# Output_Mixer_v1_1.net
KiCad netlist of a schematic drawn in EAGLE
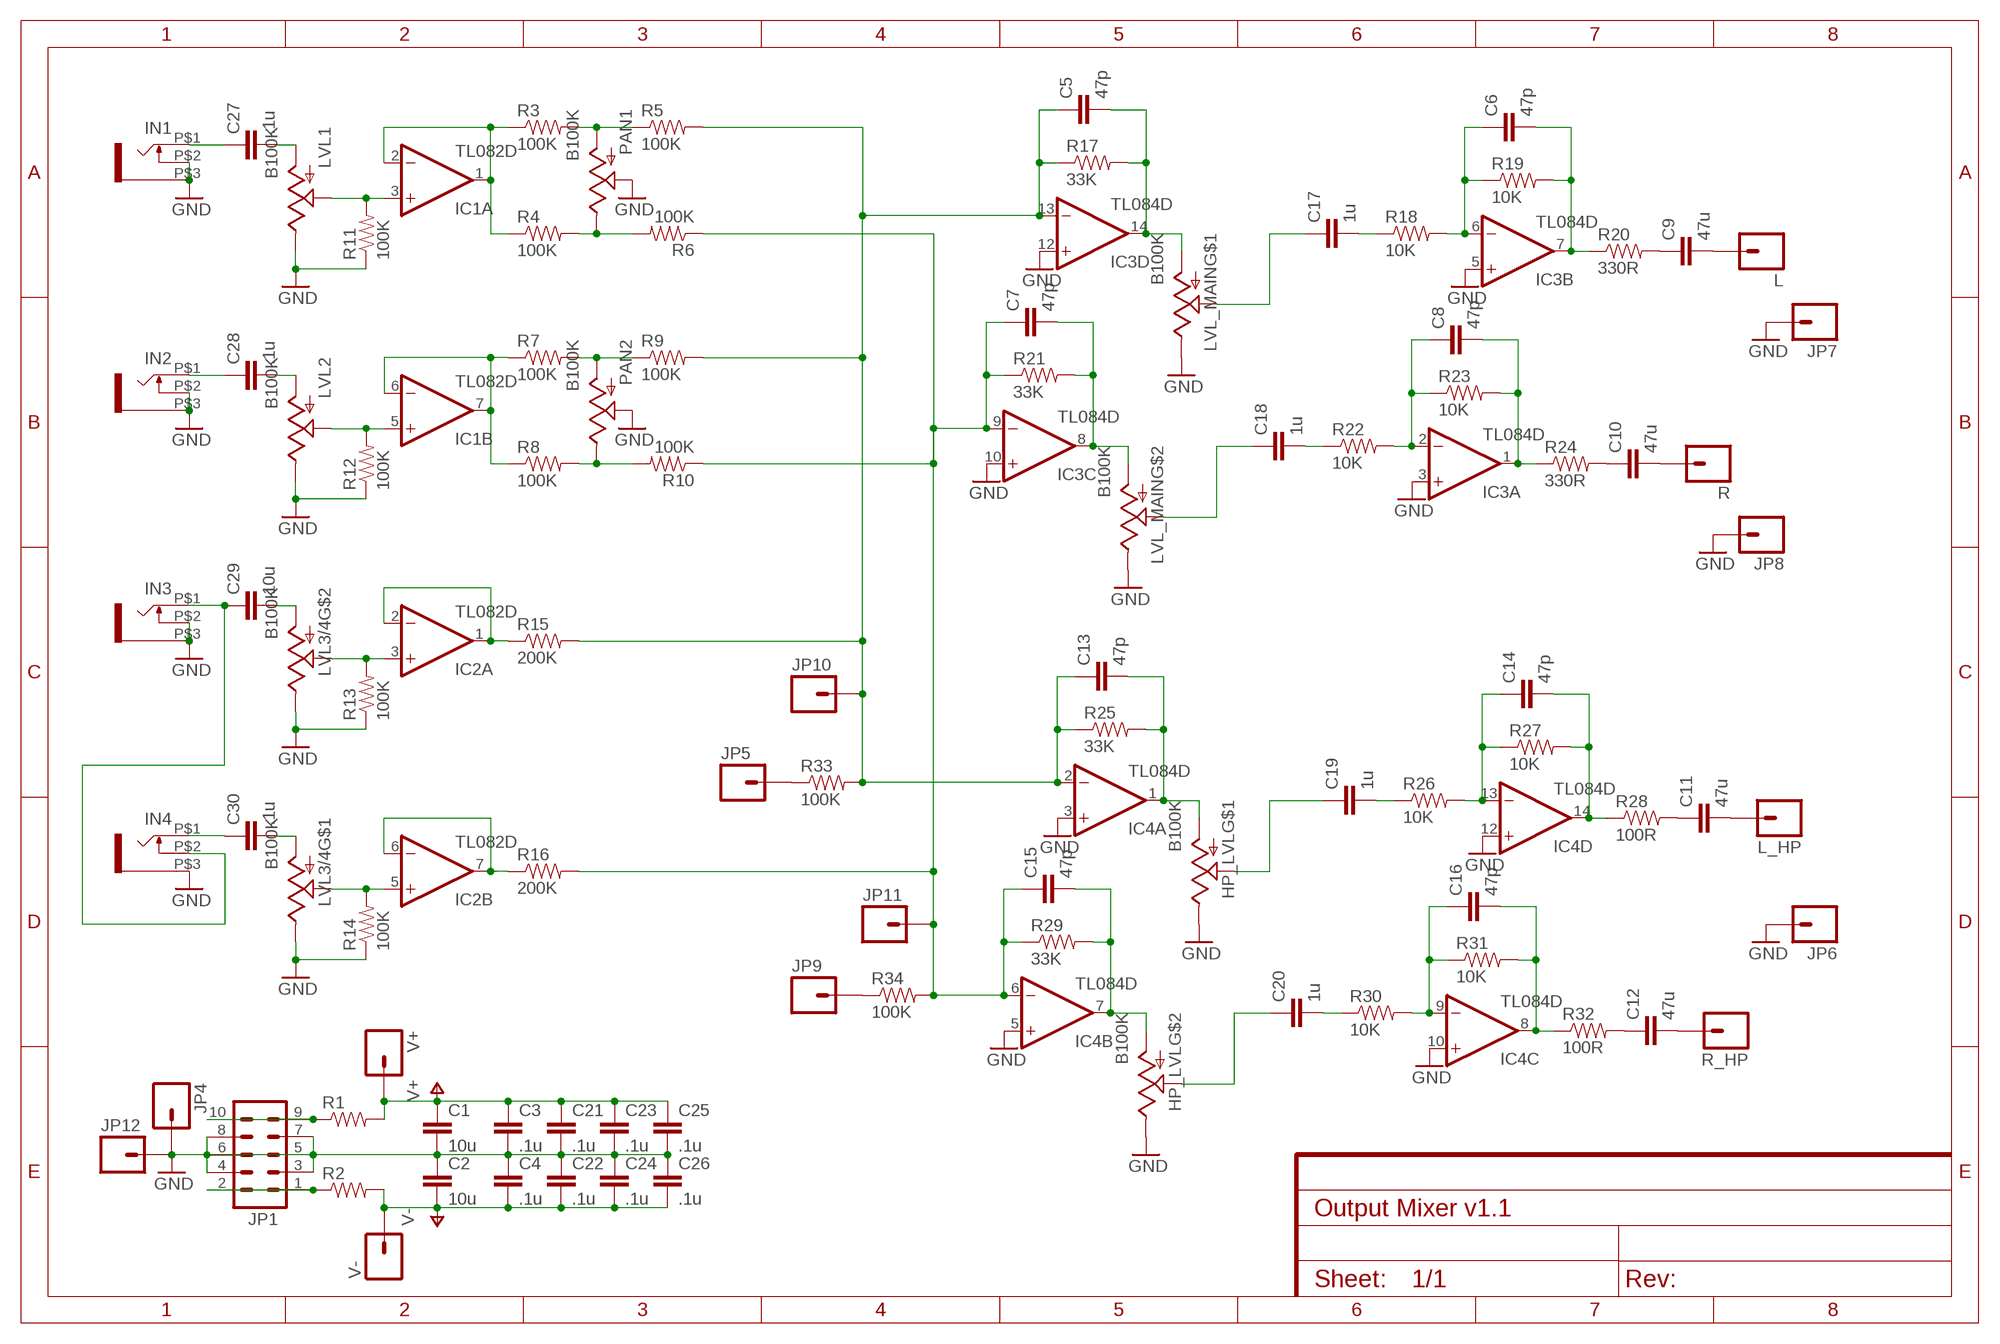
[diagram p0: schematic, sheet 1]

(export (version "E")
  (design (tool "Eeschema 10.0.6"))
  (components
    (comp (ref "C1")
      (value "10u")
      (footprint "eagle-import:1206")
      (libsource (lib "eagle-import") (part "CAP1206"))
    )
    (comp (ref "C2")
      (value "10u")
      (footprint "eagle-import:1206")
      (libsource (lib "eagle-import") (part "CAP1206"))
    )
    (comp (ref "C3")
      (value ".1u")
      (footprint "eagle-import:0805")
      (libsource (lib "eagle-import") (part "CAP0805"))
    )
    (comp (ref "C4")
      (value ".1u")
      (footprint "eagle-import:0805")
      (libsource (lib "eagle-import") (part "CAP0805"))
    )
    (comp (ref "C5")
      (value "47p")
      (footprint "eagle-import:0805")
      (libsource (lib "eagle-import") (part "CAP0805"))
    )
    (comp (ref "C6")
      (value "47p")
      (footprint "eagle-import:0805")
      (libsource (lib "eagle-import") (part "CAP0805"))
    )
    (comp (ref "C7")
      (value "47p")
      (footprint "eagle-import:0805")
      (libsource (lib "eagle-import") (part "CAP0805"))
    )
    (comp (ref "C8")
      (value "47p")
      (footprint "eagle-import:0805")
      (libsource (lib "eagle-import") (part "CAP0805"))
    )
    (comp (ref "C9")
      (value "47u")
      (footprint "eagle-import:1206")
      (libsource (lib "eagle-import") (part "CAP1206"))
    )
    (comp (ref "C10")
      (value "47u")
      (footprint "eagle-import:1206")
      (libsource (lib "eagle-import") (part "CAP1206"))
    )
    (comp (ref "C11")
      (value "47u")
      (footprint "eagle-import:1206")
      (libsource (lib "eagle-import") (part "CAP1206"))
    )
    (comp (ref "C12")
      (value "47u")
      (footprint "eagle-import:1206")
      (libsource (lib "eagle-import") (part "CAP1206"))
    )
    (comp (ref "C13")
      (value "47p")
      (footprint "eagle-import:0805")
      (libsource (lib "eagle-import") (part "CAP0805"))
    )
    (comp (ref "C14")
      (value "47p")
      (footprint "eagle-import:0805")
      (libsource (lib "eagle-import") (part "CAP0805"))
    )
    (comp (ref "C15")
      (value "47p")
      (footprint "eagle-import:0805")
      (libsource (lib "eagle-import") (part "CAP0805"))
    )
    (comp (ref "C16")
      (value "47p")
      (footprint "eagle-import:0805")
      (libsource (lib "eagle-import") (part "CAP0805"))
    )
    (comp (ref "C17")
      (value "1u")
      (footprint "eagle-import:0805")
      (libsource (lib "eagle-import") (part "CAP0805"))
    )
    (comp (ref "C18")
      (value "1u")
      (footprint "eagle-import:0805")
      (libsource (lib "eagle-import") (part "CAP0805"))
    )
    (comp (ref "C19")
      (value "1u")
      (footprint "eagle-import:0805")
      (libsource (lib "eagle-import") (part "CAP0805"))
    )
    (comp (ref "C20")
      (value "1u")
      (footprint "eagle-import:0805")
      (libsource (lib "eagle-import") (part "CAP0805"))
    )
    (comp (ref "C21")
      (value ".1u")
      (footprint "eagle-import:0805")
      (libsource (lib "eagle-import") (part "CAP0805"))
    )
    (comp (ref "C22")
      (value ".1u")
      (footprint "eagle-import:0805")
      (libsource (lib "eagle-import") (part "CAP0805"))
    )
    (comp (ref "C23")
      (value ".1u")
      (footprint "eagle-import:0805")
      (libsource (lib "eagle-import") (part "CAP0805"))
    )
    (comp (ref "C24")
      (value ".1u")
      (footprint "eagle-import:0805")
      (libsource (lib "eagle-import") (part "CAP0805"))
    )
    (comp (ref "C25")
      (value ".1u")
      (footprint "eagle-import:0805")
      (libsource (lib "eagle-import") (part "CAP0805"))
    )
    (comp (ref "C26")
      (value ".1u")
      (footprint "eagle-import:0805")
      (libsource (lib "eagle-import") (part "CAP0805"))
    )
    (comp (ref "C27")
      (value ".1u")
      (footprint "eagle-import:1206")
      (libsource (lib "eagle-import") (part "CAP1206"))
    )
    (comp (ref "C28")
      (value ".1u")
      (footprint "eagle-import:1206")
      (libsource (lib "eagle-import") (part "CAP1206"))
    )
    (comp (ref "C29")
      (value "10u")
      (footprint "eagle-import:1206")
      (libsource (lib "eagle-import") (part "CAP1206"))
    )
    (comp (ref "C30")
      (value ".1u")
      (footprint "eagle-import:1206")
      (libsource (lib "eagle-import") (part "CAP1206"))
    )
    (comp (ref "HP_LVL")
      (value "B100K")
      (footprint "eagle-import:ALPS_ALPHA_POT_DUAL")
      (libsource (lib "eagle-import") (part "POT_DUAL_ALPHA"))
    )
    (comp (ref "IC1")
      (value "TL082D")
      (footprint "eagle-import:SO08")
      (libsource (lib "eagle-import") (part "TL082D"))
    )
    (comp (ref "IC2")
      (value "TL082D")
      (footprint "eagle-import:SO08")
      (libsource (lib "eagle-import") (part "TL082D"))
    )
    (comp (ref "IC3")
      (value "TL084D")
      (footprint "eagle-import:SO14")
      (libsource (lib "eagle-import") (part "TL084D"))
    )
    (comp (ref "IC4")
      (value "TL084D")
      (footprint "eagle-import:SO14")
      (libsource (lib "eagle-import") (part "TL084D"))
    )
    (comp (ref "IN1")
      (value "WQP-PJ301M-12_JACK")
      (footprint "eagle-import:WQP-PJ301M-12_JACK")
      (libsource (lib "eagle-import") (part "WQP-PJ301M-12_JACK"))
    )
    (comp (ref "IN2")
      (value "WQP-PJ301M-12_JACK")
      (footprint "eagle-import:WQP-PJ301M-12_JACK")
      (libsource (lib "eagle-import") (part "WQP-PJ301M-12_JACK"))
    )
    (comp (ref "IN3")
      (value "WQP-PJ301M-12_JACK")
      (footprint "eagle-import:WQP-PJ301M-12_JACK")
      (libsource (lib "eagle-import") (part "WQP-PJ301M-12_JACK"))
    )
    (comp (ref "IN4")
      (value "WQP-PJ301M-12_JACK")
      (footprint "eagle-import:WQP-PJ301M-12_JACK")
      (libsource (lib "eagle-import") (part "WQP-PJ301M-12_JACK"))
    )
    (comp (ref "JP1")
      (value "M05X2PTH")
      (footprint "eagle-import:AVR_ICSP")
      (libsource (lib "eagle-import") (part "M05X2PTH"))
    )
    (comp (ref "JP4")
      (value "M01PTH")
      (footprint "eagle-import:1X01")
      (libsource (lib "eagle-import") (part "M01PTH"))
    )
    (comp (ref "JP5")
      (value "M01PTH")
      (footprint "eagle-import:1X01")
      (libsource (lib "eagle-import") (part "M01PTH"))
    )
    (comp (ref "JP6")
      (value "M01PTH")
      (footprint "eagle-import:1X01")
      (libsource (lib "eagle-import") (part "M01PTH"))
    )
    (comp (ref "JP7")
      (value "M01PTH")
      (footprint "eagle-import:1X01")
      (libsource (lib "eagle-import") (part "M01PTH"))
    )
    (comp (ref "JP8")
      (value "M01PTH")
      (footprint "eagle-import:1X01")
      (libsource (lib "eagle-import") (part "M01PTH"))
    )
    (comp (ref "JP9")
      (value "M01PTH")
      (footprint "eagle-import:1X01")
      (libsource (lib "eagle-import") (part "M01PTH"))
    )
    (comp (ref "JP10")
      (value "M01PTH")
      (footprint "eagle-import:1X01")
      (libsource (lib "eagle-import") (part "M01PTH"))
    )
    (comp (ref "JP11")
      (value "M01PTH")
      (footprint "eagle-import:1X01")
      (libsource (lib "eagle-import") (part "M01PTH"))
    )
    (comp (ref "JP12")
      (value "M01PTH")
      (footprint "eagle-import:1X01")
      (libsource (lib "eagle-import") (part "M01PTH"))
    )
    (comp (ref "L")
      (value "M01PTH")
      (footprint "eagle-import:1X01")
      (libsource (lib "eagle-import") (part "M01PTH"))
    )
    (comp (ref "LVL1")
      (value "B100K")
      (footprint "eagle-import:ALPS_POT")
      (libsource (lib "eagle-import") (part "POT"))
    )
    (comp (ref "LVL2")
      (value "B100K")
      (footprint "eagle-import:ALPS_POT")
      (libsource (lib "eagle-import") (part "POT"))
    )
    (comp (ref "LVL3/4")
      (value "B100K")
      (footprint "eagle-import:ALPS_ALPHA_POT_DUAL")
      (libsource (lib "eagle-import") (part "POT_DUAL_ALPHA"))
    )
    (comp (ref "LVL_MAIN")
      (value "B100K")
      (footprint "eagle-import:ALPS_ALPHA_POT_DUAL")
      (libsource (lib "eagle-import") (part "POT_DUAL_ALPHA"))
    )
    (comp (ref "L_HP")
      (value "M01PTH")
      (footprint "eagle-import:1X01")
      (libsource (lib "eagle-import") (part "M01PTH"))
    )
    (comp (ref "PAN1")
      (value "B100K")
      (footprint "eagle-import:ALPS_POT")
      (libsource (lib "eagle-import") (part "POT"))
    )
    (comp (ref "PAN2")
      (value "B100K")
      (footprint "eagle-import:ALPS_POT")
      (libsource (lib "eagle-import") (part "POT"))
    )
    (comp (ref "R")
      (value "M01PTH")
      (footprint "eagle-import:1X01")
      (libsource (lib "eagle-import") (part "M01PTH"))
    )
    (comp (ref "R1")
      (value "RESISTOR0805-RES")
      (footprint "eagle-import:0805")
      (libsource (lib "eagle-import") (part "RESISTOR0805-RES"))
    )
    (comp (ref "R2")
      (value "RESISTOR0805-RES")
      (footprint "eagle-import:0805")
      (libsource (lib "eagle-import") (part "RESISTOR0805-RES"))
    )
    (comp (ref "R3")
      (value "100K")
      (footprint "eagle-import:0805")
      (libsource (lib "eagle-import") (part "RESISTOR0805-RES"))
    )
    (comp (ref "R4")
      (value "100K")
      (footprint "eagle-import:0805")
      (libsource (lib "eagle-import") (part "RESISTOR0805-RES"))
    )
    (comp (ref "R5")
      (value "100K")
      (footprint "eagle-import:0805")
      (libsource (lib "eagle-import") (part "RESISTOR0805-RES"))
    )
    (comp (ref "R6")
      (value "100K")
      (footprint "eagle-import:0805")
      (libsource (lib "eagle-import") (part "RESISTOR0805-RES"))
    )
    (comp (ref "R7")
      (value "100K")
      (footprint "eagle-import:0805")
      (libsource (lib "eagle-import") (part "RESISTOR0805-RES"))
    )
    (comp (ref "R8")
      (value "100K")
      (footprint "eagle-import:0805")
      (libsource (lib "eagle-import") (part "RESISTOR0805-RES"))
    )
    (comp (ref "R9")
      (value "100K")
      (footprint "eagle-import:0805")
      (libsource (lib "eagle-import") (part "RESISTOR0805-RES"))
    )
    (comp (ref "R10")
      (value "100K")
      (footprint "eagle-import:0805")
      (libsource (lib "eagle-import") (part "RESISTOR0805-RES"))
    )
    (comp (ref "R11")
      (value "100K")
      (footprint "eagle-import:0805")
      (libsource (lib "eagle-import") (part "RESISTOR0805-RES"))
    )
    (comp (ref "R12")
      (value "100K")
      (footprint "eagle-import:0805")
      (libsource (lib "eagle-import") (part "RESISTOR0805-RES"))
    )
    (comp (ref "R13")
      (value "100K")
      (footprint "eagle-import:0805")
      (libsource (lib "eagle-import") (part "RESISTOR0805-RES"))
    )
    (comp (ref "R14")
      (value "100K")
      (footprint "eagle-import:0805")
      (libsource (lib "eagle-import") (part "RESISTOR0805-RES"))
    )
    (comp (ref "R15")
      (value "200K")
      (footprint "eagle-import:0805")
      (libsource (lib "eagle-import") (part "RESISTOR0805-RES"))
    )
    (comp (ref "R16")
      (value "200K")
      (footprint "eagle-import:0805")
      (libsource (lib "eagle-import") (part "RESISTOR0805-RES"))
    )
    (comp (ref "R17")
      (value "33K")
      (footprint "eagle-import:0805")
      (libsource (lib "eagle-import") (part "RESISTOR0805-RES"))
    )
    (comp (ref "R18")
      (value "10K")
      (footprint "eagle-import:0805")
      (libsource (lib "eagle-import") (part "RESISTOR0805-RES"))
    )
    (comp (ref "R19")
      (value "10K")
      (footprint "eagle-import:0805")
      (libsource (lib "eagle-import") (part "RESISTOR0805-RES"))
    )
    (comp (ref "R20")
      (value "330R")
      (footprint "eagle-import:0805")
      (libsource (lib "eagle-import") (part "RESISTOR0805-RES"))
    )
    (comp (ref "R21")
      (value "33K")
      (footprint "eagle-import:0805")
      (libsource (lib "eagle-import") (part "RESISTOR0805-RES"))
    )
    (comp (ref "R22")
      (value "10K")
      (footprint "eagle-import:0805")
      (libsource (lib "eagle-import") (part "RESISTOR0805-RES"))
    )
    (comp (ref "R23")
      (value "10K")
      (footprint "eagle-import:0805")
      (libsource (lib "eagle-import") (part "RESISTOR0805-RES"))
    )
    (comp (ref "R24")
      (value "330R")
      (footprint "eagle-import:0805")
      (libsource (lib "eagle-import") (part "RESISTOR0805-RES"))
    )
    (comp (ref "R25")
      (value "33K")
      (footprint "eagle-import:0805")
      (libsource (lib "eagle-import") (part "RESISTOR0805-RES"))
    )
    (comp (ref "R26")
      (value "10K")
      (footprint "eagle-import:0805")
      (libsource (lib "eagle-import") (part "RESISTOR0805-RES"))
    )
    (comp (ref "R27")
      (value "10K")
      (footprint "eagle-import:0805")
      (libsource (lib "eagle-import") (part "RESISTOR0805-RES"))
    )
    (comp (ref "R28")
      (value "100R")
      (footprint "eagle-import:0805")
      (libsource (lib "eagle-import") (part "RESISTOR0805-RES"))
    )
    (comp (ref "R29")
      (value "33K")
      (footprint "eagle-import:0805")
      (libsource (lib "eagle-import") (part "RESISTOR0805-RES"))
    )
    (comp (ref "R30")
      (value "10K")
      (footprint "eagle-import:0805")
      (libsource (lib "eagle-import") (part "RESISTOR0805-RES"))
    )
    (comp (ref "R31")
      (value "10K")
      (footprint "eagle-import:0805")
      (libsource (lib "eagle-import") (part "RESISTOR0805-RES"))
    )
    (comp (ref "R32")
      (value "100R")
      (footprint "eagle-import:0805")
      (libsource (lib "eagle-import") (part "RESISTOR0805-RES"))
    )
    (comp (ref "R33")
      (value "100K")
      (footprint "eagle-import:0805")
      (libsource (lib "eagle-import") (part "RESISTOR0805-RES"))
    )
    (comp (ref "R34")
      (value "100K")
      (footprint "eagle-import:0805")
      (libsource (lib "eagle-import") (part "RESISTOR0805-RES"))
    )
    (comp (ref "R_HP")
      (value "M01PTH")
      (footprint "eagle-import:1X01")
      (libsource (lib "eagle-import") (part "M01PTH"))
    )
    (comp (ref "V+")
      (value "M01PTH")
      (footprint "eagle-import:1X01")
      (libsource (lib "eagle-import") (part "M01PTH"))
    )
    (comp (ref "V-")
      (value "M01PTH")
      (footprint "eagle-import:1X01")
      (libsource (lib "eagle-import") (part "M01PTH"))
    )
  )
  (nets
    (net (code "1") (name "GND") (class "Default")
      (node (ref "C1") (pin "2") (pinfunction "2_2") (pintype "passive"))
      (node (ref "C2") (pin "1") (pinfunction "1_1") (pintype "passive"))
      (node (ref "C21") (pin "2") (pinfunction "2_2") (pintype "passive"))
      (node (ref "C22") (pin "1") (pinfunction "1_1") (pintype "passive"))
      (node (ref "C23") (pin "2") (pinfunction "2_2") (pintype "passive"))
      (node (ref "C24") (pin "1") (pinfunction "1_1") (pintype "passive"))
      (node (ref "C25") (pin "2") (pinfunction "2_2") (pintype "passive"))
      (node (ref "C26") (pin "1") (pinfunction "1_1") (pintype "passive"))
      (node (ref "C3") (pin "2") (pinfunction "2_2") (pintype "passive"))
      (node (ref "C4") (pin "1") (pinfunction "1_1") (pintype "passive"))
      (node (ref "HP_LVL") (pin "P$1") (pinfunction "E_P$1") (pintype "passive"))
      (node (ref "HP_LVL") (pin "P$4") (pinfunction "E_P$4") (pintype "passive"))
      (node (ref "IC3") (pin "10") (pinfunction "+IN_10") (pintype "input"))
      (node (ref "IC3") (pin "12") (pinfunction "+IN_12") (pintype "input"))
      (node (ref "IC3") (pin "3") (pinfunction "+IN_3") (pintype "input"))
      (node (ref "IC3") (pin "5") (pinfunction "+IN_5") (pintype "input"))
      (node (ref "IC4") (pin "10") (pinfunction "+IN_10") (pintype "input"))
      (node (ref "IC4") (pin "12") (pinfunction "+IN_12") (pintype "input"))
      (node (ref "IC4") (pin "3") (pinfunction "+IN_3") (pintype "input"))
      (node (ref "IC4") (pin "5") (pinfunction "+IN_5") (pintype "input"))
      (node (ref "IN1") (pin "P$2") (pinfunction "3_P$2") (pintype "passive"))
      (node (ref "IN1") (pin "P$3") (pinfunction "1_P$3") (pintype "passive"))
      (node (ref "IN2") (pin "P$2") (pinfunction "3_P$2") (pintype "passive"))
      (node (ref "IN2") (pin "P$3") (pinfunction "1_P$3") (pintype "passive"))
      (node (ref "IN3") (pin "P$2") (pinfunction "3_P$2") (pintype "passive"))
      (node (ref "IN3") (pin "P$3") (pinfunction "1_P$3") (pintype "passive"))
      (node (ref "IN4") (pin "P$3") (pinfunction "1_P$3") (pintype "passive"))
      (node (ref "JP1") (pin "3") (pinfunction "3_3") (pintype "passive"))
      (node (ref "JP1") (pin "4") (pinfunction "4_4") (pintype "passive"))
      (node (ref "JP1") (pin "5") (pinfunction "5_5") (pintype "passive"))
      (node (ref "JP1") (pin "6") (pinfunction "6_6") (pintype "passive"))
      (node (ref "JP1") (pin "7") (pinfunction "7_7") (pintype "passive"))
      (node (ref "JP1") (pin "8") (pinfunction "8_8") (pintype "passive"))
      (node (ref "JP12") (pin "1") (pinfunction "1_1") (pintype "passive"))
      (node (ref "JP4") (pin "1") (pinfunction "1_1") (pintype "passive"))
      (node (ref "JP6") (pin "1") (pinfunction "1_1") (pintype "passive"))
      (node (ref "JP7") (pin "1") (pinfunction "1_1") (pintype "passive"))
      (node (ref "JP8") (pin "1") (pinfunction "1_1") (pintype "passive"))
      (node (ref "LVL1") (pin "P$1") (pinfunction "E_P$1") (pintype "passive"))
      (node (ref "LVL2") (pin "P$1") (pinfunction "E_P$1") (pintype "passive"))
      (node (ref "LVL3/4") (pin "P$1") (pinfunction "E_P$1") (pintype "passive"))
      (node (ref "LVL3/4") (pin "P$4") (pinfunction "E_P$4") (pintype "passive"))
      (node (ref "LVL_MAIN") (pin "P$1") (pinfunction "E_P$1") (pintype "passive"))
      (node (ref "LVL_MAIN") (pin "P$4") (pinfunction "E_P$4") (pintype "passive"))
      (node (ref "PAN1") (pin "P$2") (pinfunction "S_P$2") (pintype "passive"))
      (node (ref "PAN2") (pin "P$2") (pinfunction "S_P$2") (pintype "passive"))
      (node (ref "R11") (pin "1") (pinfunction "1_1") (pintype "passive"))
      (node (ref "R12") (pin "1") (pinfunction "1_1") (pintype "passive"))
      (node (ref "R13") (pin "1") (pinfunction "1_1") (pintype "passive"))
      (node (ref "R14") (pin "1") (pinfunction "1_1") (pintype "passive"))
    )
    (net (code "2") (name "Net-(C9-Pad1)") (class "Default")
      (node (ref "C9") (pin "1") (pinfunction "1_1") (pintype "passive"))
      (node (ref "R20") (pin "2") (pinfunction "2_2") (pintype "passive"))
    )
    (net (code "3") (name "Net-(C9-Pad2)") (class "Default")
      (node (ref "C9") (pin "2") (pinfunction "2_2") (pintype "passive"))
      (node (ref "L") (pin "1") (pinfunction "1_1") (pintype "passive"))
    )
    (net (code "4") (name "Net-(C10-Pad1)") (class "Default")
      (node (ref "C10") (pin "1") (pinfunction "1_1") (pintype "passive"))
      (node (ref "R24") (pin "2") (pinfunction "2_2") (pintype "passive"))
    )
    (net (code "5") (name "Net-(C10-Pad2)") (class "Default")
      (node (ref "C10") (pin "2") (pinfunction "2_2") (pintype "passive"))
      (node (ref "R") (pin "1") (pinfunction "1_1") (pintype "passive"))
    )
    (net (code "6") (name "Net-(C11-Pad1)") (class "Default")
      (node (ref "C11") (pin "1") (pinfunction "1_1") (pintype "passive"))
      (node (ref "R28") (pin "2") (pinfunction "2_2") (pintype "passive"))
    )
    (net (code "7") (name "Net-(C11-Pad2)") (class "Default")
      (node (ref "C11") (pin "2") (pinfunction "2_2") (pintype "passive"))
      (node (ref "L_HP") (pin "1") (pinfunction "1_1") (pintype "passive"))
    )
    (net (code "8") (name "Net-(C12-Pad1)") (class "Default")
      (node (ref "C12") (pin "1") (pinfunction "1_1") (pintype "passive"))
      (node (ref "R32") (pin "2") (pinfunction "2_2") (pintype "passive"))
    )
    (net (code "9") (name "Net-(C12-Pad2)") (class "Default")
      (node (ref "C12") (pin "2") (pinfunction "2_2") (pintype "passive"))
      (node (ref "R_HP") (pin "1") (pinfunction "1_1") (pintype "passive"))
    )
    (net (code "10") (name "Net-(C17-Pad2)") (class "Default")
      (node (ref "C17") (pin "2") (pinfunction "2_2") (pintype "passive"))
      (node (ref "R18") (pin "1") (pinfunction "1_1") (pintype "passive"))
    )
    (net (code "11") (name "Net-(C18-Pad2)") (class "Default")
      (node (ref "C18") (pin "2") (pinfunction "2_2") (pintype "passive"))
      (node (ref "R22") (pin "1") (pinfunction "1_1") (pintype "passive"))
    )
    (net (code "12") (name "Net-(C19-Pad2)") (class "Default")
      (node (ref "C19") (pin "2") (pinfunction "2_2") (pintype "passive"))
      (node (ref "R26") (pin "1") (pinfunction "1_1") (pintype "passive"))
    )
    (net (code "13") (name "Net-(C20-Pad2)") (class "Default")
      (node (ref "C20") (pin "2") (pinfunction "2_2") (pintype "passive"))
      (node (ref "R30") (pin "1") (pinfunction "1_1") (pintype "passive"))
    )
    (net (code "14") (name "Net-(HP_LVLA-A)") (class "Default")
      (node (ref "C13") (pin "2") (pinfunction "2_2") (pintype "passive"))
      (node (ref "HP_LVL") (pin "P$3") (pinfunction "A_P$3") (pintype "passive"))
      (node (ref "IC4") (pin "1") (pinfunction "OUT_1") (pintype "output"))
      (node (ref "R25") (pin "2") (pinfunction "2_2") (pintype "passive"))
    )
    (net (code "15") (name "Net-(HP_LVLA-S)") (class "Default")
      (node (ref "C19") (pin "1") (pinfunction "1_1") (pintype "passive"))
      (node (ref "HP_LVL") (pin "P$2") (pinfunction "S_P$2") (pintype "passive"))
    )
    (net (code "16") (name "Net-(HP_LVLB-A)") (class "Default")
      (node (ref "C15") (pin "2") (pinfunction "2_2") (pintype "passive"))
      (node (ref "HP_LVL") (pin "P$6") (pinfunction "A_P$6") (pintype "passive"))
      (node (ref "IC4") (pin "7") (pinfunction "OUT_7") (pintype "output"))
      (node (ref "R29") (pin "2") (pinfunction "2_2") (pintype "passive"))
    )
    (net (code "17") (name "Net-(HP_LVLB-S)") (class "Default")
      (node (ref "C20") (pin "1") (pinfunction "1_1") (pintype "passive"))
      (node (ref "HP_LVL") (pin "P$5") (pinfunction "S_P$5") (pintype "passive"))
    )
    (net (code "18") (name "Net-(IC1A-+IN)") (class "Default")
      (node (ref "IC1") (pin "3") (pinfunction "+IN_3") (pintype "input"))
      (node (ref "LVL1") (pin "P$2") (pinfunction "S_P$2") (pintype "passive"))
      (node (ref "R11") (pin "2") (pinfunction "2_2") (pintype "passive"))
    )
    (net (code "19") (name "Net-(IC1A--IN)") (class "Default")
      (node (ref "IC1") (pin "1") (pinfunction "OUT_1") (pintype "output"))
      (node (ref "IC1") (pin "2") (pinfunction "-IN_2") (pintype "input"))
      (node (ref "R3") (pin "1") (pinfunction "1_1") (pintype "passive"))
      (node (ref "R4") (pin "1") (pinfunction "1_1") (pintype "passive"))
    )
    (net (code "20") (name "Net-(IC1B-+IN)") (class "Default")
      (node (ref "IC1") (pin "5") (pinfunction "+IN_5") (pintype "input"))
      (node (ref "LVL2") (pin "P$2") (pinfunction "S_P$2") (pintype "passive"))
      (node (ref "R12") (pin "2") (pinfunction "2_2") (pintype "passive"))
    )
    (net (code "21") (name "Net-(IC1B--IN)") (class "Default")
      (node (ref "IC1") (pin "6") (pinfunction "-IN_6") (pintype "input"))
      (node (ref "IC1") (pin "7") (pinfunction "OUT_7") (pintype "output"))
      (node (ref "R7") (pin "1") (pinfunction "1_1") (pintype "passive"))
      (node (ref "R8") (pin "1") (pinfunction "1_1") (pintype "passive"))
    )
    (net (code "22") (name "Net-(IC2A-+IN)") (class "Default")
      (node (ref "IC2") (pin "3") (pinfunction "+IN_3") (pintype "input"))
      (node (ref "LVL3/4") (pin "P$5") (pinfunction "S_P$5") (pintype "passive"))
      (node (ref "R13") (pin "2") (pinfunction "2_2") (pintype "passive"))
    )
    (net (code "23") (name "Net-(IC2A--IN)") (class "Default")
      (node (ref "IC2") (pin "1") (pinfunction "OUT_1") (pintype "output"))
      (node (ref "IC2") (pin "2") (pinfunction "-IN_2") (pintype "input"))
      (node (ref "R15") (pin "1") (pinfunction "1_1") (pintype "passive"))
    )
    (net (code "24") (name "Net-(IC2B-+IN)") (class "Default")
      (node (ref "IC2") (pin "5") (pinfunction "+IN_5") (pintype "input"))
      (node (ref "LVL3/4") (pin "P$2") (pinfunction "S_P$2") (pintype "passive"))
      (node (ref "R14") (pin "2") (pinfunction "2_2") (pintype "passive"))
    )
    (net (code "25") (name "Net-(IC2B--IN)") (class "Default")
      (node (ref "IC2") (pin "6") (pinfunction "-IN_6") (pintype "input"))
      (node (ref "IC2") (pin "7") (pinfunction "OUT_7") (pintype "output"))
      (node (ref "R16") (pin "1") (pinfunction "1_1") (pintype "passive"))
    )
    (net (code "26") (name "Net-(IC3A--IN)") (class "Default")
      (node (ref "C8") (pin "1") (pinfunction "1_1") (pintype "passive"))
      (node (ref "IC3") (pin "2") (pinfunction "-IN_2") (pintype "input"))
      (node (ref "R22") (pin "2") (pinfunction "2_2") (pintype "passive"))
      (node (ref "R23") (pin "1") (pinfunction "1_1") (pintype "passive"))
    )
    (net (code "27") (name "Net-(IC3A-OUT)") (class "Default")
      (node (ref "C8") (pin "2") (pinfunction "2_2") (pintype "passive"))
      (node (ref "IC3") (pin "1") (pinfunction "OUT_1") (pintype "output"))
      (node (ref "R23") (pin "2") (pinfunction "2_2") (pintype "passive"))
      (node (ref "R24") (pin "1") (pinfunction "1_1") (pintype "passive"))
    )
    (net (code "28") (name "Net-(IC3B--IN)") (class "Default")
      (node (ref "C6") (pin "1") (pinfunction "1_1") (pintype "passive"))
      (node (ref "IC3") (pin "6") (pinfunction "-IN_6") (pintype "input"))
      (node (ref "R18") (pin "2") (pinfunction "2_2") (pintype "passive"))
      (node (ref "R19") (pin "1") (pinfunction "1_1") (pintype "passive"))
    )
    (net (code "29") (name "Net-(IC3B-OUT)") (class "Default")
      (node (ref "C6") (pin "2") (pinfunction "2_2") (pintype "passive"))
      (node (ref "IC3") (pin "7") (pinfunction "OUT_7") (pintype "output"))
      (node (ref "R19") (pin "2") (pinfunction "2_2") (pintype "passive"))
      (node (ref "R20") (pin "1") (pinfunction "1_1") (pintype "passive"))
    )
    (net (code "30") (name "Net-(IC3C--IN)") (class "Default")
      (node (ref "C15") (pin "1") (pinfunction "1_1") (pintype "passive"))
      (node (ref "C7") (pin "1") (pinfunction "1_1") (pintype "passive"))
      (node (ref "IC3") (pin "9") (pinfunction "-IN_9") (pintype "input"))
      (node (ref "IC4") (pin "6") (pinfunction "-IN_6") (pintype "input"))
      (node (ref "JP11") (pin "1") (pinfunction "1_1") (pintype "passive"))
      (node (ref "R10") (pin "1") (pinfunction "1_1") (pintype "passive"))
      (node (ref "R16") (pin "2") (pinfunction "2_2") (pintype "passive"))
      (node (ref "R21") (pin "1") (pinfunction "1_1") (pintype "passive"))
      (node (ref "R29") (pin "1") (pinfunction "1_1") (pintype "passive"))
      (node (ref "R34") (pin "2") (pinfunction "2_2") (pintype "passive"))
      (node (ref "R6") (pin "1") (pinfunction "1_1") (pintype "passive"))
    )
    (net (code "31") (name "Net-(IC3C-OUT)") (class "Default")
      (node (ref "C7") (pin "2") (pinfunction "2_2") (pintype "passive"))
      (node (ref "IC3") (pin "8") (pinfunction "OUT_8") (pintype "output"))
      (node (ref "LVL_MAIN") (pin "P$6") (pinfunction "A_P$6") (pintype "passive"))
      (node (ref "R21") (pin "2") (pinfunction "2_2") (pintype "passive"))
    )
    (net (code "32") (name "Net-(IC3D--IN)") (class "Default")
      (node (ref "C13") (pin "1") (pinfunction "1_1") (pintype "passive"))
      (node (ref "C5") (pin "1") (pinfunction "1_1") (pintype "passive"))
      (node (ref "IC3") (pin "13") (pinfunction "-IN_13") (pintype "input"))
      (node (ref "IC4") (pin "2") (pinfunction "-IN_2") (pintype "input"))
      (node (ref "JP10") (pin "1") (pinfunction "1_1") (pintype "passive"))
      (node (ref "R15") (pin "2") (pinfunction "2_2") (pintype "passive"))
      (node (ref "R17") (pin "1") (pinfunction "1_1") (pintype "passive"))
      (node (ref "R25") (pin "1") (pinfunction "1_1") (pintype "passive"))
      (node (ref "R33") (pin "2") (pinfunction "2_2") (pintype "passive"))
      (node (ref "R5") (pin "2") (pinfunction "2_2") (pintype "passive"))
      (node (ref "R9") (pin "2") (pinfunction "2_2") (pintype "passive"))
    )
    (net (code "33") (name "Net-(IC3D-OUT)") (class "Default")
      (node (ref "C5") (pin "2") (pinfunction "2_2") (pintype "passive"))
      (node (ref "IC3") (pin "14") (pinfunction "OUT_14") (pintype "output"))
      (node (ref "LVL_MAIN") (pin "P$3") (pinfunction "A_P$3") (pintype "passive"))
      (node (ref "R17") (pin "2") (pinfunction "2_2") (pintype "passive"))
    )
    (net (code "34") (name "Net-(IC4C--IN)") (class "Default")
      (node (ref "C16") (pin "1") (pinfunction "1_1") (pintype "passive"))
      (node (ref "IC4") (pin "9") (pinfunction "-IN_9") (pintype "input"))
      (node (ref "R30") (pin "2") (pinfunction "2_2") (pintype "passive"))
      (node (ref "R31") (pin "1") (pinfunction "1_1") (pintype "passive"))
    )
    (net (code "35") (name "Net-(IC4C-OUT)") (class "Default")
      (node (ref "C16") (pin "2") (pinfunction "2_2") (pintype "passive"))
      (node (ref "IC4") (pin "8") (pinfunction "OUT_8") (pintype "output"))
      (node (ref "R31") (pin "2") (pinfunction "2_2") (pintype "passive"))
      (node (ref "R32") (pin "1") (pinfunction "1_1") (pintype "passive"))
    )
    (net (code "36") (name "Net-(IC4D--IN)") (class "Default")
      (node (ref "C14") (pin "1") (pinfunction "1_1") (pintype "passive"))
      (node (ref "IC4") (pin "13") (pinfunction "-IN_13") (pintype "input"))
      (node (ref "R26") (pin "2") (pinfunction "2_2") (pintype "passive"))
      (node (ref "R27") (pin "1") (pinfunction "1_1") (pintype "passive"))
    )
    (net (code "37") (name "Net-(IC4D-OUT)") (class "Default")
      (node (ref "C14") (pin "2") (pinfunction "2_2") (pintype "passive"))
      (node (ref "IC4") (pin "14") (pinfunction "OUT_14") (pintype "output"))
      (node (ref "R27") (pin "2") (pinfunction "2_2") (pintype "passive"))
      (node (ref "R28") (pin "1") (pinfunction "1_1") (pintype "passive"))
    )
    (net (code "38") (name "Net-(IN1-2)") (class "Default")
      (node (ref "C27") (pin "1") (pinfunction "1_1") (pintype "passive"))
      (node (ref "IN1") (pin "P$1") (pinfunction "2_P$1") (pintype "passive"))
    )
    (net (code "39") (name "Net-(IN2-2)") (class "Default")
      (node (ref "C28") (pin "1") (pinfunction "1_1") (pintype "passive"))
      (node (ref "IN2") (pin "P$1") (pinfunction "2_P$1") (pintype "passive"))
    )
    (net (code "40") (name "Net-(IN3-2)") (class "Default")
      (node (ref "C29") (pin "1") (pinfunction "1_1") (pintype "passive"))
      (node (ref "IN3") (pin "P$1") (pinfunction "2_P$1") (pintype "passive"))
      (node (ref "IN4") (pin "P$2") (pinfunction "3_P$2") (pintype "passive"))
    )
    (net (code "41") (name "Net-(IN4-2)") (class "Default")
      (node (ref "C30") (pin "1") (pinfunction "1_1") (pintype "passive"))
      (node (ref "IN4") (pin "P$1") (pinfunction "2_P$1") (pintype "passive"))
    )
    (net (code "42") (name "Net-(JP1-Pad1)") (class "Default")
      (node (ref "JP1") (pin "1") (pinfunction "1_1") (pintype "passive"))
      (node (ref "JP1") (pin "2") (pinfunction "2_2") (pintype "passive"))
      (node (ref "R2") (pin "1") (pinfunction "1_1") (pintype "passive"))
    )
    (net (code "43") (name "Net-(JP1-Pad10)") (class "Default")
      (node (ref "JP1") (pin "10") (pinfunction "10_10") (pintype "passive"))
      (node (ref "JP1") (pin "9") (pinfunction "9_9") (pintype "passive"))
      (node (ref "R1") (pin "1") (pinfunction "1_1") (pintype "passive"))
    )
    (net (code "44") (name "Net-(JP5-Pad1)") (class "Default")
      (node (ref "JP5") (pin "1") (pinfunction "1_1") (pintype "passive"))
      (node (ref "R33") (pin "1") (pinfunction "1_1") (pintype "passive"))
    )
    (net (code "45") (name "Net-(JP9-Pad1)") (class "Default")
      (node (ref "JP9") (pin "1") (pinfunction "1_1") (pintype "passive"))
      (node (ref "R34") (pin "1") (pinfunction "1_1") (pintype "passive"))
    )
    (net (code "46") (name "Net-(LVL1-A)") (class "Default")
      (node (ref "C27") (pin "2") (pinfunction "2_2") (pintype "passive"))
      (node (ref "LVL1") (pin "P$3") (pinfunction "A_P$3") (pintype "passive"))
    )
    (net (code "47") (name "Net-(LVL2-A)") (class "Default")
      (node (ref "C28") (pin "2") (pinfunction "2_2") (pintype "passive"))
      (node (ref "LVL2") (pin "P$3") (pinfunction "A_P$3") (pintype "passive"))
    )
    (net (code "48") (name "Net-(LVL3/4A-A)") (class "Default")
      (node (ref "C30") (pin "2") (pinfunction "2_2") (pintype "passive"))
      (node (ref "LVL3/4") (pin "P$3") (pinfunction "A_P$3") (pintype "passive"))
    )
    (net (code "49") (name "Net-(LVL3/4B-A)") (class "Default")
      (node (ref "C29") (pin "2") (pinfunction "2_2") (pintype "passive"))
      (node (ref "LVL3/4") (pin "P$6") (pinfunction "A_P$6") (pintype "passive"))
    )
    (net (code "50") (name "Net-(LVL_MAINA-S)") (class "Default")
      (node (ref "C17") (pin "1") (pinfunction "1_1") (pintype "passive"))
      (node (ref "LVL_MAIN") (pin "P$2") (pinfunction "S_P$2") (pintype "passive"))
    )
    (net (code "51") (name "Net-(LVL_MAINB-S)") (class "Default")
      (node (ref "C18") (pin "1") (pinfunction "1_1") (pintype "passive"))
      (node (ref "LVL_MAIN") (pin "P$5") (pinfunction "S_P$5") (pintype "passive"))
    )
    (net (code "52") (name "Net-(PAN1-A)") (class "Default")
      (node (ref "PAN1") (pin "P$3") (pinfunction "A_P$3") (pintype "passive"))
      (node (ref "R3") (pin "2") (pinfunction "2_2") (pintype "passive"))
      (node (ref "R5") (pin "1") (pinfunction "1_1") (pintype "passive"))
    )
    (net (code "53") (name "Net-(PAN1-E)") (class "Default")
      (node (ref "PAN1") (pin "P$1") (pinfunction "E_P$1") (pintype "passive"))
      (node (ref "R4") (pin "2") (pinfunction "2_2") (pintype "passive"))
      (node (ref "R6") (pin "2") (pinfunction "2_2") (pintype "passive"))
    )
    (net (code "54") (name "Net-(PAN2-A)") (class "Default")
      (node (ref "PAN2") (pin "P$3") (pinfunction "A_P$3") (pintype "passive"))
      (node (ref "R7") (pin "2") (pinfunction "2_2") (pintype "passive"))
      (node (ref "R9") (pin "1") (pinfunction "1_1") (pintype "passive"))
    )
    (net (code "55") (name "Net-(PAN2-E)") (class "Default")
      (node (ref "PAN2") (pin "P$1") (pinfunction "E_P$1") (pintype "passive"))
      (node (ref "R10") (pin "2") (pinfunction "2_2") (pintype "passive"))
      (node (ref "R8") (pin "2") (pinfunction "2_2") (pintype "passive"))
    )
    (net (code "56") (name "V+") (class "Default")
      (node (ref "C1") (pin "1") (pinfunction "1_1") (pintype "passive"))
      (node (ref "C21") (pin "1") (pinfunction "1_1") (pintype "passive"))
      (node (ref "C23") (pin "1") (pinfunction "1_1") (pintype "passive"))
      (node (ref "C25") (pin "1") (pinfunction "1_1") (pintype "passive"))
      (node (ref "C3") (pin "1") (pinfunction "1_1") (pintype "passive"))
      (node (ref "R1") (pin "2") (pinfunction "2_2") (pintype "passive"))
      (node (ref "V+") (pin "1") (pinfunction "1_1") (pintype "passive"))
    )
    (net (code "57") (name "V-") (class "Default")
      (node (ref "C2") (pin "2") (pinfunction "2_2") (pintype "passive"))
      (node (ref "C22") (pin "2") (pinfunction "2_2") (pintype "passive"))
      (node (ref "C24") (pin "2") (pinfunction "2_2") (pintype "passive"))
      (node (ref "C26") (pin "2") (pinfunction "2_2") (pintype "passive"))
      (node (ref "C4") (pin "2") (pinfunction "2_2") (pintype "passive"))
      (node (ref "R2") (pin "2") (pinfunction "2_2") (pintype "passive"))
      (node (ref "V-") (pin "1") (pinfunction "1_1") (pintype "passive"))
    )
  )
)
